# ir_beacon.net
KiCad netlist of a schematic drawn in EAGLE
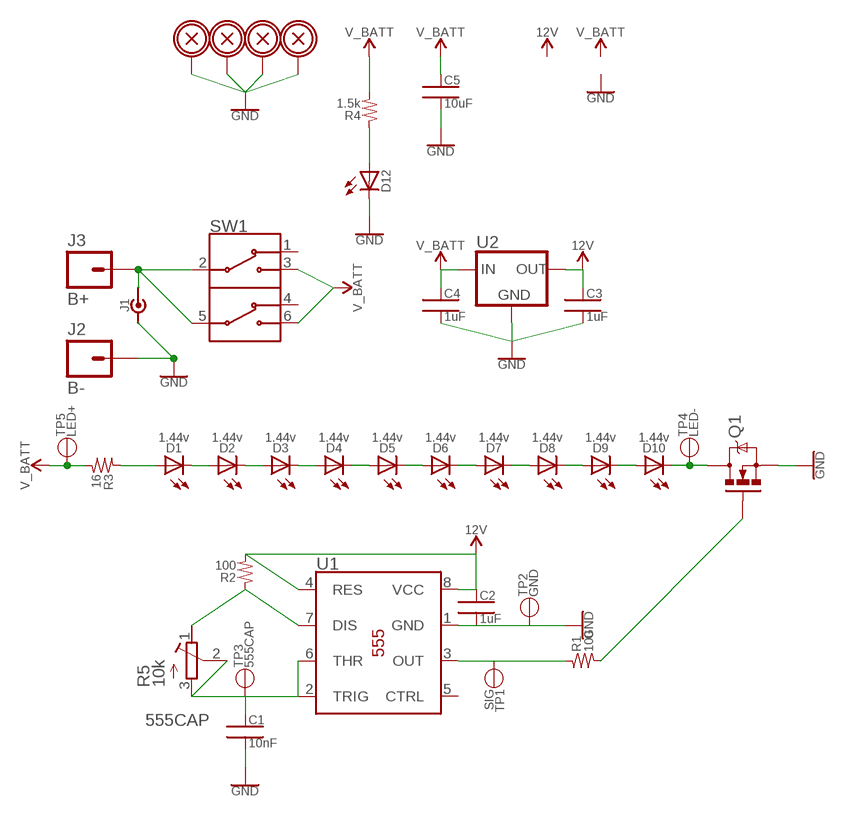
[diagram p0: schematic, sheet 1]

(export (version "E")
  (design (tool "Eeschema 10.0.6"))
  (components
    (comp (ref "C1")
      (value "10nF")
      (footprint "eagle-import:CAP-PTH-.1_")
      (libsource (lib "eagle-import") (part "CAP_PTH_SMALL_.1{dblquote}"))
    )
    (comp (ref "C2")
      (value "1uF")
      (footprint "eagle-import:0805")
      (libsource (lib "eagle-import") (part "CAP_SMD_0805"))
    )
    (comp (ref "C3")
      (value "1uF")
      (footprint "eagle-import:0805")
      (libsource (lib "eagle-import") (part "CAP_SMD_0805"))
    )
    (comp (ref "C4")
      (value "1uF")
      (footprint "eagle-import:0805")
      (libsource (lib "eagle-import") (part "CAP_SMD_0805"))
    )
    (comp (ref "C5")
      (value "10uF")
      (footprint "eagle-import:0805")
      (libsource (lib "eagle-import") (part "CAP_SMD_0805"))
    )
    (comp (ref "D1")
      (value "1.44v")
      (footprint "eagle-import:PLCC-2")
      (libsource (lib "eagle-import") (part "LED_PLCC-2"))
    )
    (comp (ref "D2")
      (value "1.44v")
      (footprint "eagle-import:PLCC-2")
      (libsource (lib "eagle-import") (part "LED_PLCC-2"))
    )
    (comp (ref "D3")
      (value "1.44v")
      (footprint "eagle-import:PLCC-2")
      (libsource (lib "eagle-import") (part "LED_PLCC-2"))
    )
    (comp (ref "D4")
      (value "1.44v")
      (footprint "eagle-import:PLCC-2")
      (libsource (lib "eagle-import") (part "LED_PLCC-2"))
    )
    (comp (ref "D5")
      (value "1.44v")
      (footprint "eagle-import:PLCC-2")
      (libsource (lib "eagle-import") (part "LED_PLCC-2"))
    )
    (comp (ref "D6")
      (value "1.44v")
      (footprint "eagle-import:PLCC-2")
      (libsource (lib "eagle-import") (part "LED_PLCC-2"))
    )
    (comp (ref "D7")
      (value "1.44v")
      (footprint "eagle-import:PLCC-2")
      (libsource (lib "eagle-import") (part "LED_PLCC-2"))
    )
    (comp (ref "D8")
      (value "1.44v")
      (footprint "eagle-import:PLCC-2")
      (libsource (lib "eagle-import") (part "LED_PLCC-2"))
    )
    (comp (ref "D9")
      (value "1.44v")
      (footprint "eagle-import:PLCC-2")
      (libsource (lib "eagle-import") (part "LED_PLCC-2"))
    )
    (comp (ref "D10")
      (value "1.44v")
      (footprint "eagle-import:PLCC-2")
      (libsource (lib "eagle-import") (part "LED_PLCC-2"))
    )
    (comp (ref "D12")
      (value "LED1206")
      (footprint "eagle-import:LED-1206")
      (libsource (lib "eagle-import") (part "LED1206"))
    )
    (comp (ref "H1")
      (value "BOLTHOLE_M3")
      (footprint "eagle-import:M3_HOLE")
      (libsource (lib "eagle-import") (part "BOLTHOLE_M3"))
    )
    (comp (ref "H2")
      (value "BOLTHOLE_M3")
      (footprint "eagle-import:M3_HOLE")
      (libsource (lib "eagle-import") (part "BOLTHOLE_M3"))
    )
    (comp (ref "H3")
      (value "BOLTHOLE_M3")
      (footprint "eagle-import:M3_HOLE")
      (libsource (lib "eagle-import") (part "BOLTHOLE_M3"))
    )
    (comp (ref "H4")
      (value "BOLTHOLE_M3")
      (footprint "eagle-import:M3_HOLE")
      (libsource (lib "eagle-import") (part "BOLTHOLE_M3"))
    )
    (comp (ref "J1")
      (value "PJ-082BH")
      (footprint "eagle-import:PJ-082BH")
      (libsource (lib "eagle-import") (part "PJ-082BH"))
    )
    (comp (ref "J2")
      (value "B-")
      (footprint "eagle-import:14AWG_PTH")
      (libsource (lib "eagle-import") (part "14AWG_PTH"))
    )
    (comp (ref "J3")
      (value "B+")
      (footprint "eagle-import:14AWG_PTH")
      (libsource (lib "eagle-import") (part "14AWG_PTH"))
    )
    (comp (ref "Q1")
      (value "MOSFET_N-CHANNEL_DPAK")
      (footprint "eagle-import:DPAK")
      (libsource (lib "eagle-import") (part "MOSFET_N-CHANNEL_DPAK"))
    )
    (comp (ref "R1")
      (value "100")
      (footprint "eagle-import:0805")
      (libsource (lib "eagle-import") (part "RES_SMD_0805"))
    )
    (comp (ref "R2")
      (value "100")
      (footprint "eagle-import:0805")
      (libsource (lib "eagle-import") (part "RES_SMD_0805"))
    )
    (comp (ref "R3")
      (value "16")
      (footprint "eagle-import:1206")
      (libsource (lib "eagle-import") (part "RES_SMD_1206"))
    )
    (comp (ref "R4")
      (value "1.5k")
      (footprint "eagle-import:0805")
      (libsource (lib "eagle-import") (part "RES_SMD_0805"))
    )
    (comp (ref "R5")
      (value "10k")
      (footprint "eagle-import:3296W")
      (libsource (lib "eagle-import") (part "3296W"))
    )
    (comp (ref "SW1")
      (value "CNK-L202_MS02")
      (footprint "eagle-import:CNK-L202XXXMS02XXX")
      (libsource (lib "eagle-import") (part "CNK-L202_MS02"))
    )
    (comp (ref "TP1")
      (value "SIG")
      (footprint "eagle-import:1X01")
      (libsource (lib "eagle-import") (part "TESTPOINT_A"))
    )
    (comp (ref "TP2")
      (value "GND")
      (footprint "eagle-import:1X01")
      (libsource (lib "eagle-import") (part "TESTPOINT_A"))
    )
    (comp (ref "TP3")
      (value "555CAP")
      (footprint "eagle-import:1X01")
      (libsource (lib "eagle-import") (part "TESTPOINT_A"))
    )
    (comp (ref "TP4")
      (value "LED-")
      (footprint "eagle-import:1X01")
      (libsource (lib "eagle-import") (part "TESTPOINT_A"))
    )
    (comp (ref "TP5")
      (value "LED+")
      (footprint "eagle-import:1X01")
      (libsource (lib "eagle-import") (part "TESTPOINT_A"))
    )
    (comp (ref "U1")
      (value "555_TIMER_DIP8")
      (footprint "eagle-import:DIL08")
      (libsource (lib "eagle-import") (part "555_TIMER_DIP8"))
    )
    (comp (ref "U2")
      (value "78XX_VREG_DPAK")
      (footprint "eagle-import:DPAK")
      (libsource (lib "eagle-import") (part "78XX_VREG_DPAK"))
    )
  )
  (nets
    (net (code "1") (name "/555CAP") (class "Default")
      (node (ref "C1") (pin "1") (pinfunction "1_1") (pintype "passive"))
      (node (ref "R5") (pin "2") (pinfunction "S_2") (pintype "passive"))
      (node (ref "R5") (pin "3") (pinfunction "A_3") (pintype "passive"))
      (node (ref "TP3") (pin "1") (pinfunction "TP_1") (pintype "bidirectional"))
      (node (ref "U1") (pin "2") (pinfunction "TRIG_2") (pintype "bidirectional"))
      (node (ref "U1") (pin "6") (pinfunction "THR_6") (pintype "bidirectional"))
    )
    (net (code "2") (name "12V") (class "Default")
      (node (ref "C2") (pin "1") (pinfunction "1_1") (pintype "passive"))
      (node (ref "C3") (pin "1") (pinfunction "1_1") (pintype "passive"))
      (node (ref "R2") (pin "2") (pinfunction "2_2") (pintype "passive"))
      (node (ref "U1") (pin "4") (pinfunction "RES_4") (pintype "bidirectional"))
      (node (ref "U1") (pin "8") (pinfunction "VCC_8") (pintype "bidirectional"))
      (node (ref "U2") (pin "3") (pinfunction "OUT_3") (pintype "passive"))
    )
    (net (code "3") (name "GND") (class "Default")
      (node (ref "C1") (pin "2") (pinfunction "2_2") (pintype "passive"))
      (node (ref "C2") (pin "2") (pinfunction "2_2") (pintype "passive"))
      (node (ref "C3") (pin "2") (pinfunction "2_2") (pintype "passive"))
      (node (ref "C4") (pin "2") (pinfunction "2_2") (pintype "passive"))
      (node (ref "C5") (pin "2") (pinfunction "2_2") (pintype "passive"))
      (node (ref "D12") (pin "C") (pinfunction "C_C") (pintype "passive"))
      (node (ref "H1") (pin "P") (pinfunction "P_P") (pintype "bidirectional"))
      (node (ref "H2") (pin "P") (pinfunction "P_P") (pintype "bidirectional"))
      (node (ref "H3") (pin "P") (pinfunction "P_P") (pintype "bidirectional"))
      (node (ref "H4") (pin "P") (pinfunction "P_P") (pintype "bidirectional"))
      (node (ref "J1") (pin "2") (pinfunction "2_2") (pintype "bidirectional"))
      (node (ref "J1") (pin "SH1") (pinfunction "2_SH1") (pintype "bidirectional"))
      (node (ref "J1") (pin "SH2") (pinfunction "2_SH2") (pintype "bidirectional"))
      (node (ref "J1") (pin "SH3") (pinfunction "2_SH3") (pintype "bidirectional"))
      (node (ref "J1") (pin "SH4") (pinfunction "2_SH4") (pintype "bidirectional"))
      (node (ref "J2") (pin "P") (pinfunction "1_P") (pintype "passive"))
      (node (ref "Q1") (pin "3") (pinfunction "S_3") (pintype "passive"))
      (node (ref "TP2") (pin "1") (pinfunction "TP_1") (pintype "bidirectional"))
      (node (ref "U1") (pin "1") (pinfunction "GND_1") (pintype "bidirectional"))
      (node (ref "U2") (pin "4") (pinfunction "GND_4") (pintype "input"))
    )
    (net (code "4") (name "Net-(D1-PadA)") (class "Default")
      (node (ref "D1") (pin "A") (pinfunction "A_A") (pintype "passive"))
      (node (ref "R3") (pin "1") (pinfunction "1_1") (pintype "passive"))
    )
    (net (code "5") (name "Net-(D1-PadC)") (class "Default")
      (node (ref "D1") (pin "C") (pinfunction "C_C") (pintype "passive"))
      (node (ref "D2") (pin "A") (pinfunction "A_A") (pintype "passive"))
    )
    (net (code "6") (name "Net-(D2-PadC)") (class "Default")
      (node (ref "D2") (pin "C") (pinfunction "C_C") (pintype "passive"))
      (node (ref "D3") (pin "A") (pinfunction "A_A") (pintype "passive"))
    )
    (net (code "7") (name "Net-(D3-PadC)") (class "Default")
      (node (ref "D3") (pin "C") (pinfunction "C_C") (pintype "passive"))
      (node (ref "D4") (pin "A") (pinfunction "A_A") (pintype "passive"))
    )
    (net (code "8") (name "Net-(D4-PadC)") (class "Default")
      (node (ref "D4") (pin "C") (pinfunction "C_C") (pintype "passive"))
      (node (ref "D5") (pin "A") (pinfunction "A_A") (pintype "passive"))
    )
    (net (code "9") (name "Net-(D5-PadC)") (class "Default")
      (node (ref "D5") (pin "C") (pinfunction "C_C") (pintype "passive"))
      (node (ref "D6") (pin "A") (pinfunction "A_A") (pintype "passive"))
    )
    (net (code "10") (name "Net-(D6-PadC)") (class "Default")
      (node (ref "D6") (pin "C") (pinfunction "C_C") (pintype "passive"))
      (node (ref "D7") (pin "A") (pinfunction "A_A") (pintype "passive"))
    )
    (net (code "11") (name "Net-(D7-PadC)") (class "Default")
      (node (ref "D7") (pin "C") (pinfunction "C_C") (pintype "passive"))
      (node (ref "D8") (pin "A") (pinfunction "A_A") (pintype "passive"))
    )
    (net (code "12") (name "Net-(D8-PadC)") (class "Default")
      (node (ref "D8") (pin "C") (pinfunction "C_C") (pintype "passive"))
      (node (ref "D9") (pin "A") (pinfunction "A_A") (pintype "passive"))
    )
    (net (code "13") (name "Net-(D10-PadA)") (class "Default")
      (node (ref "D10") (pin "A") (pinfunction "A_A") (pintype "passive"))
      (node (ref "D9") (pin "C") (pinfunction "C_C") (pintype "passive"))
    )
    (net (code "14") (name "Net-(D12-PadA)") (class "Default")
      (node (ref "D12") (pin "A") (pinfunction "A_A") (pintype "passive"))
      (node (ref "R4") (pin "1") (pinfunction "1_1") (pintype "passive"))
    )
    (net (code "15") (name "Net-(J3-1)") (class "Default")
      (node (ref "J1") (pin "1") (pinfunction "1_1") (pintype "bidirectional"))
      (node (ref "J3") (pin "P") (pinfunction "1_P") (pintype "passive"))
      (node (ref "SW1") (pin "2") (pinfunction "I1_2") (pintype "bidirectional"))
      (node (ref "SW1") (pin "5") (pinfunction "I2_5") (pintype "bidirectional"))
    )
    (net (code "16") (name "Net-(Q1-D)") (class "Default")
      (node (ref "D10") (pin "C") (pinfunction "C_C") (pintype "passive"))
      (node (ref "Q1") (pin "4") (pinfunction "D_4") (pintype "passive"))
      (node (ref "TP4") (pin "1") (pinfunction "TP_1") (pintype "bidirectional"))
    )
    (net (code "17") (name "Net-(Q1-G)") (class "Default")
      (node (ref "Q1") (pin "1") (pinfunction "G_1") (pintype "passive"))
      (node (ref "R1") (pin "2") (pinfunction "2_2") (pintype "passive"))
    )
    (net (code "18") (name "Net-(R5-E)") (class "Default")
      (node (ref "R2") (pin "1") (pinfunction "1_1") (pintype "passive"))
      (node (ref "R5") (pin "1") (pinfunction "E_1") (pintype "passive"))
      (node (ref "U1") (pin "7") (pinfunction "DIS_7") (pintype "bidirectional"))
    )
    (net (code "19") (name "Net-(TP1-TP)") (class "Default")
      (node (ref "R1") (pin "1") (pinfunction "1_1") (pintype "passive"))
      (node (ref "TP1") (pin "1") (pinfunction "TP_1") (pintype "bidirectional"))
      (node (ref "U1") (pin "3") (pinfunction "OUT_3") (pintype "bidirectional"))
    )
    (net (code "20") (name "V_BATT") (class "Default")
      (node (ref "C4") (pin "1") (pinfunction "1_1") (pintype "passive"))
      (node (ref "C5") (pin "1") (pinfunction "1_1") (pintype "passive"))
      (node (ref "R3") (pin "2") (pinfunction "2_2") (pintype "passive"))
      (node (ref "R4") (pin "2") (pinfunction "2_2") (pintype "passive"))
      (node (ref "SW1") (pin "3") (pinfunction "O1B_3") (pintype "bidirectional"))
      (node (ref "SW1") (pin "6") (pinfunction "O2B_6") (pintype "bidirectional"))
      (node (ref "TP5") (pin "1") (pinfunction "TP_1") (pintype "bidirectional"))
      (node (ref "U2") (pin "1") (pinfunction "IN_1") (pintype "input"))
    )
    (net (code "21") (name "unconnected-(SW1-O1A-Pad1)") (class "Default")
      (node (ref "SW1") (pin "1") (pinfunction "O1A_1") (pintype "bidirectional"))
    )
    (net (code "22") (name "unconnected-(SW1-O2A-Pad4)") (class "Default")
      (node (ref "SW1") (pin "4") (pinfunction "O2A_4") (pintype "bidirectional"))
    )
    (net (code "23") (name "unconnected-(U1-CTRL-Pad5)") (class "Default")
      (node (ref "U1") (pin "5") (pinfunction "CTRL_5") (pintype "bidirectional"))
    )
  )
)
